# 2012_PerfUSB.net
KiCad netlist of a schematic drawn in Altium Designer
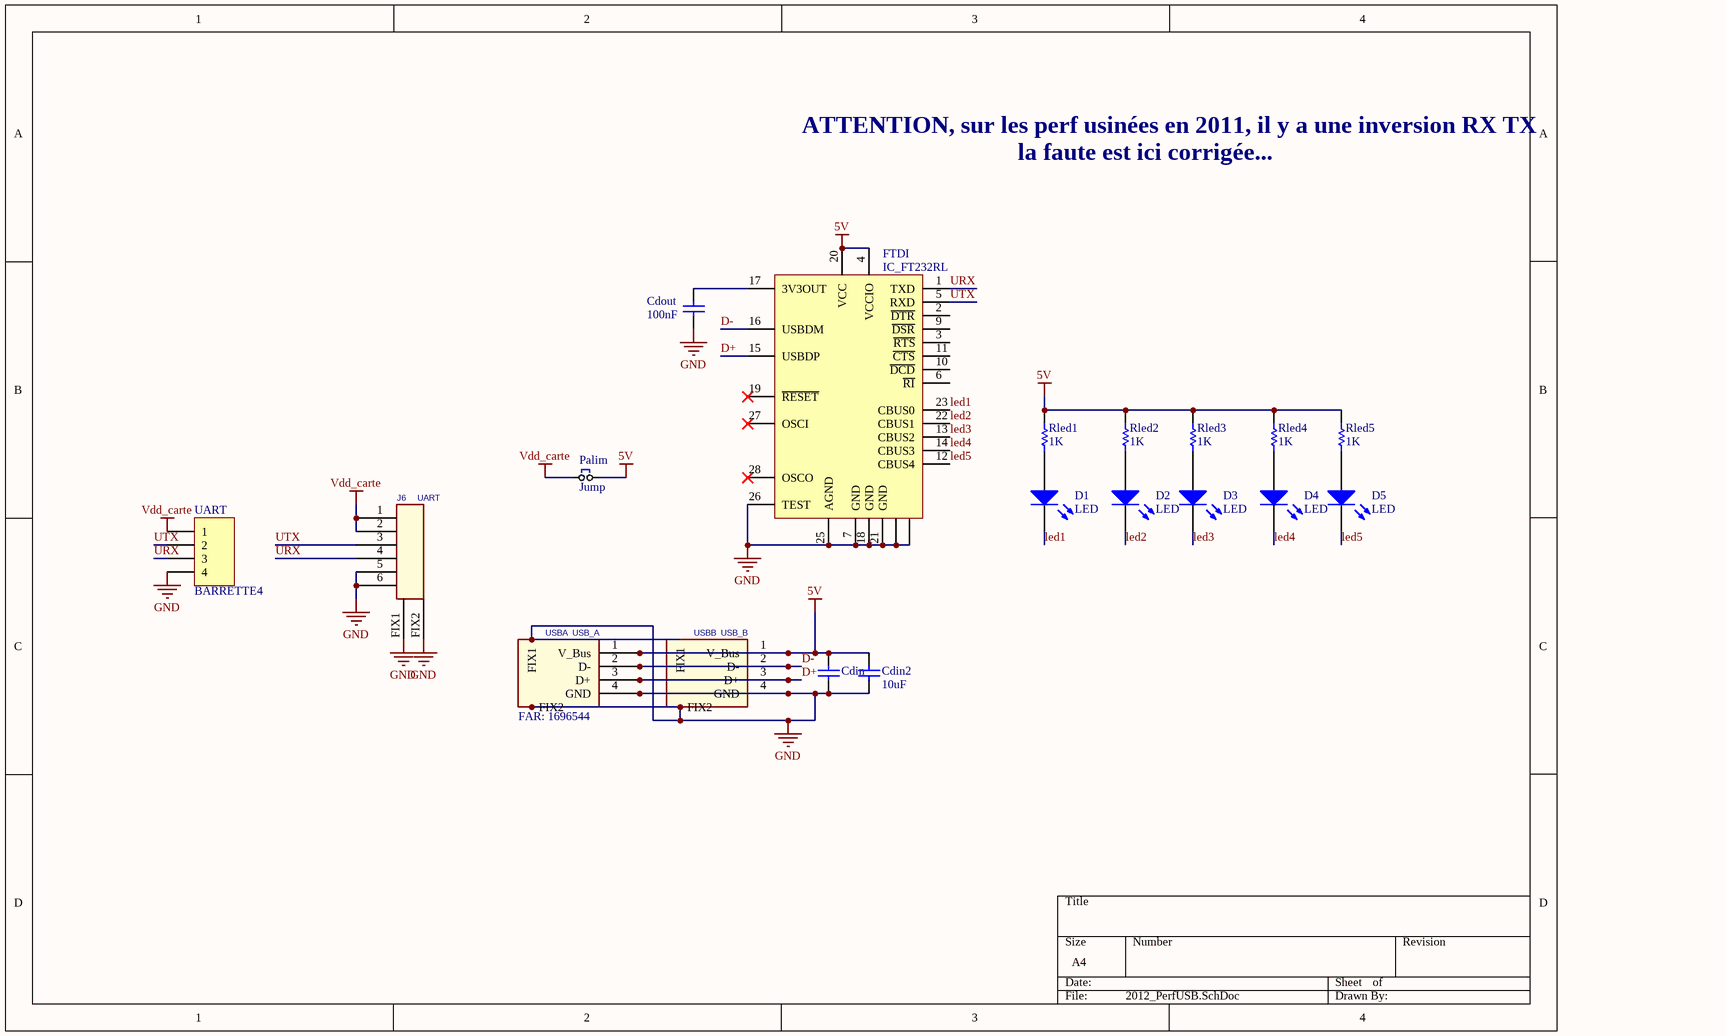
[diagram p0: 2012_PerfUSB.SchDoc]

(export (version "E")
  (design (tool "Eeschema 10.0.6"))
  (components
    (comp (ref "Cdin")
      (value "100nF")
      (footprint "C0603_N")
      (description "Capacitor")
      (fields (field (name "PUBLISHER") "Damien GUITTON"))
      (libsource (lib "") (part "Capacitor_1"))
    )
    (comp (ref "Cdin2")
      (value "10uF")
      (footprint "C1206_N")
      (description "Capacitor")
      (fields (field (name "PUBLISHER") "Altium Limited"))
      (libsource (lib "DG_Condensateur") (part "Capacitor"))
    )
    (comp (ref "Cdout")
      (value "100nF")
      (footprint "C0603_N")
      (description "Capacitor")
      (fields (field (name "PUBLISHER") "Damien GUITTON"))
      (libsource (lib "DG_discret") (part "Capacitor"))
    )
    (comp (ref "D1")
      (value "LED")
      (footprint "LED_0805")
      (description "Typical LED")
      (fields (field (name "PUBLISHER") "Altium Limited"))
      (libsource (lib "DG_LED") (part "LED"))
    )
    (comp (ref "D2")
      (value "LED")
      (footprint "LED_0805")
      (description "Typical LED")
      (fields (field (name "PUBLISHER") "Altium Limited"))
      (libsource (lib "DG_LED") (part "LED"))
    )
    (comp (ref "D3")
      (value "LED")
      (footprint "LED_0805")
      (description "Typical LED")
      (fields (field (name "PUBLISHER") "Altium Limited"))
      (libsource (lib "DG_LED") (part "LED"))
    )
    (comp (ref "D4")
      (value "LED")
      (footprint "LED_0805")
      (description "Typical LED")
      (fields (field (name "PUBLISHER") "Altium Limited"))
      (libsource (lib "DG_LED") (part "LED"))
    )
    (comp (ref "D5")
      (value "LED")
      (footprint "LED_0805")
      (description "Typical LED")
      (fields (field (name "PUBLISHER") "Altium Limited"))
      (libsource (lib "DG_LED") (part "LED"))
    )
    (comp (ref "FTDI")
      (value "IC_FT232RL")
      (footprint "SSOP28_N")
      (description "FT232R USB UART")
      (libsource (lib "Circuit intégré") (part "IC_FT232RL"))
    )
    (comp (ref "J6") (value "UART") (footprint "RJ11_6/6") (libsource (lib "*") (part "CONNECTEUR_RJ12")))
    (comp (ref "Palim")
      (value "Jump")
      (footprint "HDR1X2")
      (description "Jumper SIP2.54")
      (libsource (lib "Connecteur") (part "Jumper SIP2.54"))
    )
    (comp (ref "Rled1")
      (value "1K")
      (footprint "R1206_N")
      (description "Resistor")
      (fields (field (name "PUBLISHER") "Altium Limited"))
      (libsource (lib "DG_Resistance") (part "Resistor"))
    )
    (comp (ref "Rled2")
      (value "1K")
      (footprint "R1206_N")
      (description "Resistor")
      (fields (field (name "PUBLISHER") "Altium Limited"))
      (libsource (lib "DG_Resistance") (part "Resistor"))
    )
    (comp (ref "Rled3")
      (value "1K")
      (footprint "R1206_N")
      (description "Resistor")
      (fields (field (name "PUBLISHER") "Altium Limited"))
      (libsource (lib "DG_Resistance") (part "Resistor"))
    )
    (comp (ref "Rled4")
      (value "1K")
      (footprint "R1206_N")
      (description "Resistor")
      (fields (field (name "PUBLISHER") "Altium Limited"))
      (libsource (lib "DG_Resistance") (part "Resistor"))
    )
    (comp (ref "Rled5")
      (value "1K")
      (footprint "R1206_N")
      (description "Resistor")
      (fields (field (name "PUBLISHER") "Altium Limited"))
      (libsource (lib "DG_Resistance") (part "Resistor"))
    )
    (comp (ref "UART")
      (value "BARRETTE4")
      (footprint "HDR1X4")
      (description "Header, 4-Pin")
      (fields (field (name "PUBLISHER") "Altium Limited"))
      (libsource (lib "Connecteur") (part "HDR1X4"))
    )
    (comp (ref "USBA")
      (value "USB_A")
      (footprint "USB_A_COUDE - FAR1696544")
      (description "FAR1696544")
      (fields (field (name "FAR") "1696544"))
      (libsource (lib "*") (part "USB_B"))
    )
    (comp (ref "USBB") (value "USB_B") (footprint "USB_B_COUDE") (libsource (lib "*") (part "USB_B")))
  )
  (nets
    (net (code "1") (name "/D+") (class "Default")
      (node (ref "FTDI") (pin "15") (pinfunction "USBDP_15") (pintype "passive"))
      (node (ref "USBA") (pin "3") (pinfunction "D+_3") (pintype "passive"))
      (node (ref "USBB") (pin "3") (pinfunction "D+_3") (pintype "passive"))
    )
    (net (code "2") (name "/D-") (class "Default")
      (node (ref "FTDI") (pin "16") (pinfunction "USBDM_16") (pintype "passive"))
      (node (ref "USBA") (pin "2") (pinfunction "D-_2") (pintype "passive"))
      (node (ref "USBB") (pin "2") (pinfunction "D-_2") (pintype "passive"))
    )
    (net (code "3") (name "/URX") (class "Default")
      (node (ref "FTDI") (pin "1") (pinfunction "TXD_1") (pintype "passive"))
      (node (ref "J6") (pin "4") (pinfunction "4_4") (pintype "passive"))
      (node (ref "UART") (pin "3") (pinfunction "3_3") (pintype "passive"))
    )
    (net (code "4") (name "/UTX") (class "Default")
      (node (ref "FTDI") (pin "5") (pinfunction "RXD_5") (pintype "passive"))
      (node (ref "J6") (pin "3") (pinfunction "3_3") (pintype "passive"))
      (node (ref "UART") (pin "2") (pinfunction "2_2") (pintype "passive"))
    )
    (net (code "5") (name "/led1") (class "Default")
      (node (ref "D1") (pin "2") (pinfunction "2_2") (pintype "passive"))
      (node (ref "FTDI") (pin "23") (pinfunction "CBUS0_23") (pintype "passive"))
    )
    (net (code "6") (name "/led2") (class "Default")
      (node (ref "D2") (pin "2") (pinfunction "2_2") (pintype "passive"))
      (node (ref "FTDI") (pin "22") (pinfunction "CBUS1_22") (pintype "passive"))
    )
    (net (code "7") (name "/led3") (class "Default")
      (node (ref "D3") (pin "2") (pinfunction "2_2") (pintype "passive"))
      (node (ref "FTDI") (pin "13") (pinfunction "CBUS2_13") (pintype "passive"))
    )
    (net (code "8") (name "/led4") (class "Default")
      (node (ref "D4") (pin "2") (pinfunction "2_2") (pintype "passive"))
      (node (ref "FTDI") (pin "14") (pinfunction "CBUS3_14") (pintype "passive"))
    )
    (net (code "9") (name "/led5") (class "Default")
      (node (ref "D5") (pin "2") (pinfunction "2_2") (pintype "passive"))
      (node (ref "FTDI") (pin "12") (pinfunction "CBUS4_12") (pintype "passive"))
    )
    (net (code "10") (name "5V") (class "Default")
      (node (ref "Cdin") (pin "2") (pinfunction "2_2") (pintype "passive"))
      (node (ref "Cdin2") (pin "2") (pinfunction "2_2") (pintype "passive"))
      (node (ref "FTDI") (pin "20") (pinfunction "VCC_20") (pintype "passive"))
      (node (ref "FTDI") (pin "4") (pinfunction "VCCIO_4") (pintype "passive"))
      (node (ref "Palim") (pin "2") (pinfunction "2_2") (pintype "passive"))
      (node (ref "Rled1") (pin "2") (pinfunction "2_2") (pintype "passive"))
      (node (ref "Rled2") (pin "2") (pinfunction "2_2") (pintype "passive"))
      (node (ref "Rled3") (pin "2") (pinfunction "2_2") (pintype "passive"))
      (node (ref "Rled4") (pin "2") (pinfunction "2_2") (pintype "passive"))
      (node (ref "Rled5") (pin "2") (pinfunction "2_2") (pintype "passive"))
      (node (ref "USBA") (pin "1") (pinfunction "V_Bus_1") (pintype "passive"))
      (node (ref "USBB") (pin "1") (pinfunction "V_Bus_1") (pintype "passive"))
    )
    (net (code "11") (name "GND") (class "Default")
      (node (ref "Cdin") (pin "1") (pinfunction "1_1") (pintype "passive"))
      (node (ref "Cdin2") (pin "1") (pinfunction "1_1") (pintype "passive"))
      (node (ref "Cdout") (pin "1") (pinfunction "1_1") (pintype "passive"))
      (node (ref "FTDI") (pin "18") (pinfunction "GND_18") (pintype "passive"))
      (node (ref "FTDI") (pin "21") (pinfunction "GND_21") (pintype "passive"))
      (node (ref "FTDI") (pin "24") (pinfunction "NC_24") (pintype "passive"))
      (node (ref "FTDI") (pin "25") (pinfunction "AGND_25") (pintype "passive"))
      (node (ref "FTDI") (pin "26") (pinfunction "TEST_26") (pintype "passive"))
      (node (ref "FTDI") (pin "7") (pinfunction "GND_7") (pintype "passive"))
      (node (ref "FTDI") (pin "8") (pinfunction "NC_8") (pintype "passive"))
      (node (ref "J6") (pin "5") (pinfunction "5_5") (pintype "passive"))
      (node (ref "J6") (pin "6") (pinfunction "6_6") (pintype "passive"))
      (node (ref "J6") (pin "FIX1") (pinfunction "FIX1_FIX1") (pintype "passive"))
      (node (ref "J6") (pin "FIX2") (pinfunction "FIX2_FIX2") (pintype "passive"))
      (node (ref "UART") (pin "4") (pinfunction "4_4") (pintype "passive"))
      (node (ref "USBA") (pin "4") (pinfunction "GND_4") (pintype "passive"))
      (node (ref "USBA") (pin "FIX1") (pinfunction "FIX1_FIX1") (pintype "passive"))
      (node (ref "USBA") (pin "FIX2") (pinfunction "FIX2_FIX2") (pintype "passive"))
      (node (ref "USBB") (pin "4") (pinfunction "GND_4") (pintype "passive"))
      (node (ref "USBB") (pin "FIX1") (pinfunction "FIX1_FIX1") (pintype "passive"))
      (node (ref "USBB") (pin "FIX2") (pinfunction "FIX2_FIX2") (pintype "passive"))
    )
    (net (code "12") (name "Net-(D1-Pad1)") (class "Default")
      (node (ref "D1") (pin "1") (pinfunction "1_1") (pintype "passive"))
      (node (ref "Rled1") (pin "1") (pinfunction "1_1") (pintype "passive"))
    )
    (net (code "13") (name "Net-(D2-Pad1)") (class "Default")
      (node (ref "D2") (pin "1") (pinfunction "1_1") (pintype "passive"))
      (node (ref "Rled2") (pin "1") (pinfunction "1_1") (pintype "passive"))
    )
    (net (code "14") (name "Net-(D3-Pad1)") (class "Default")
      (node (ref "D3") (pin "1") (pinfunction "1_1") (pintype "passive"))
      (node (ref "Rled3") (pin "1") (pinfunction "1_1") (pintype "passive"))
    )
    (net (code "15") (name "Net-(D4-Pad1)") (class "Default")
      (node (ref "D4") (pin "1") (pinfunction "1_1") (pintype "passive"))
      (node (ref "Rled4") (pin "1") (pinfunction "1_1") (pintype "passive"))
    )
    (net (code "16") (name "Net-(D5-Pad1)") (class "Default")
      (node (ref "D5") (pin "1") (pinfunction "1_1") (pintype "passive"))
      (node (ref "Rled5") (pin "1") (pinfunction "1_1") (pintype "passive"))
    )
    (net (code "17") (name "Net-(FTDI-3V3OUT)") (class "Default")
      (node (ref "Cdout") (pin "2") (pinfunction "2_2") (pintype "passive"))
      (node (ref "FTDI") (pin "17") (pinfunction "3V3OUT_17") (pintype "passive"))
    )
    (net (code "18") (name "Vdd_carte") (class "Default")
      (node (ref "J6") (pin "1") (pinfunction "1_1") (pintype "passive"))
      (node (ref "J6") (pin "2") (pinfunction "2_2") (pintype "passive"))
      (node (ref "Palim") (pin "1") (pinfunction "1_1") (pintype "passive"))
      (node (ref "UART") (pin "1") (pinfunction "1_1") (pintype "passive"))
    )
    (net (code "19") (name "unconnected-(FTDI-OSCI-Pad27)") (class "Default")
      (node (ref "FTDI") (pin "27") (pinfunction "OSCI_27") (pintype "passive+no_connect"))
    )
    (net (code "20") (name "unconnected-(FTDI-OSCO-Pad28)") (class "Default")
      (node (ref "FTDI") (pin "28") (pinfunction "OSCO_28") (pintype "passive+no_connect"))
    )
    (net (code "21") (name "unconnected-(FTDI-~{CTS}-Pad11)") (class "Default")
      (node (ref "FTDI") (pin "11") (pinfunction "~{CTS}_11") (pintype "passive"))
    )
    (net (code "22") (name "unconnected-(FTDI-~{DCD}-Pad10)") (class "Default")
      (node (ref "FTDI") (pin "10") (pinfunction "~{DCD}_10") (pintype "passive"))
    )
    (net (code "23") (name "unconnected-(FTDI-~{DSR}-Pad9)") (class "Default")
      (node (ref "FTDI") (pin "9") (pinfunction "~{DSR}_9") (pintype "passive"))
    )
    (net (code "24") (name "unconnected-(FTDI-~{DTR}-Pad2)") (class "Default")
      (node (ref "FTDI") (pin "2") (pinfunction "~{DTR}_2") (pintype "passive"))
    )
    (net (code "25") (name "unconnected-(FTDI-~{RESET}-Pad19)") (class "Default")
      (node (ref "FTDI") (pin "19") (pinfunction "~{RESET}_19") (pintype "passive+no_connect"))
    )
    (net (code "26") (name "unconnected-(FTDI-~{RI}-Pad6)") (class "Default")
      (node (ref "FTDI") (pin "6") (pinfunction "~{RI}_6") (pintype "passive"))
    )
    (net (code "27") (name "unconnected-(FTDI-~{RTS}-Pad3)") (class "Default")
      (node (ref "FTDI") (pin "3") (pinfunction "~{RTS}_3") (pintype "passive"))
    )
  )
)
